# CT_Breakout_Board.net
KiCad netlist of a schematic drawn in Altium Designer
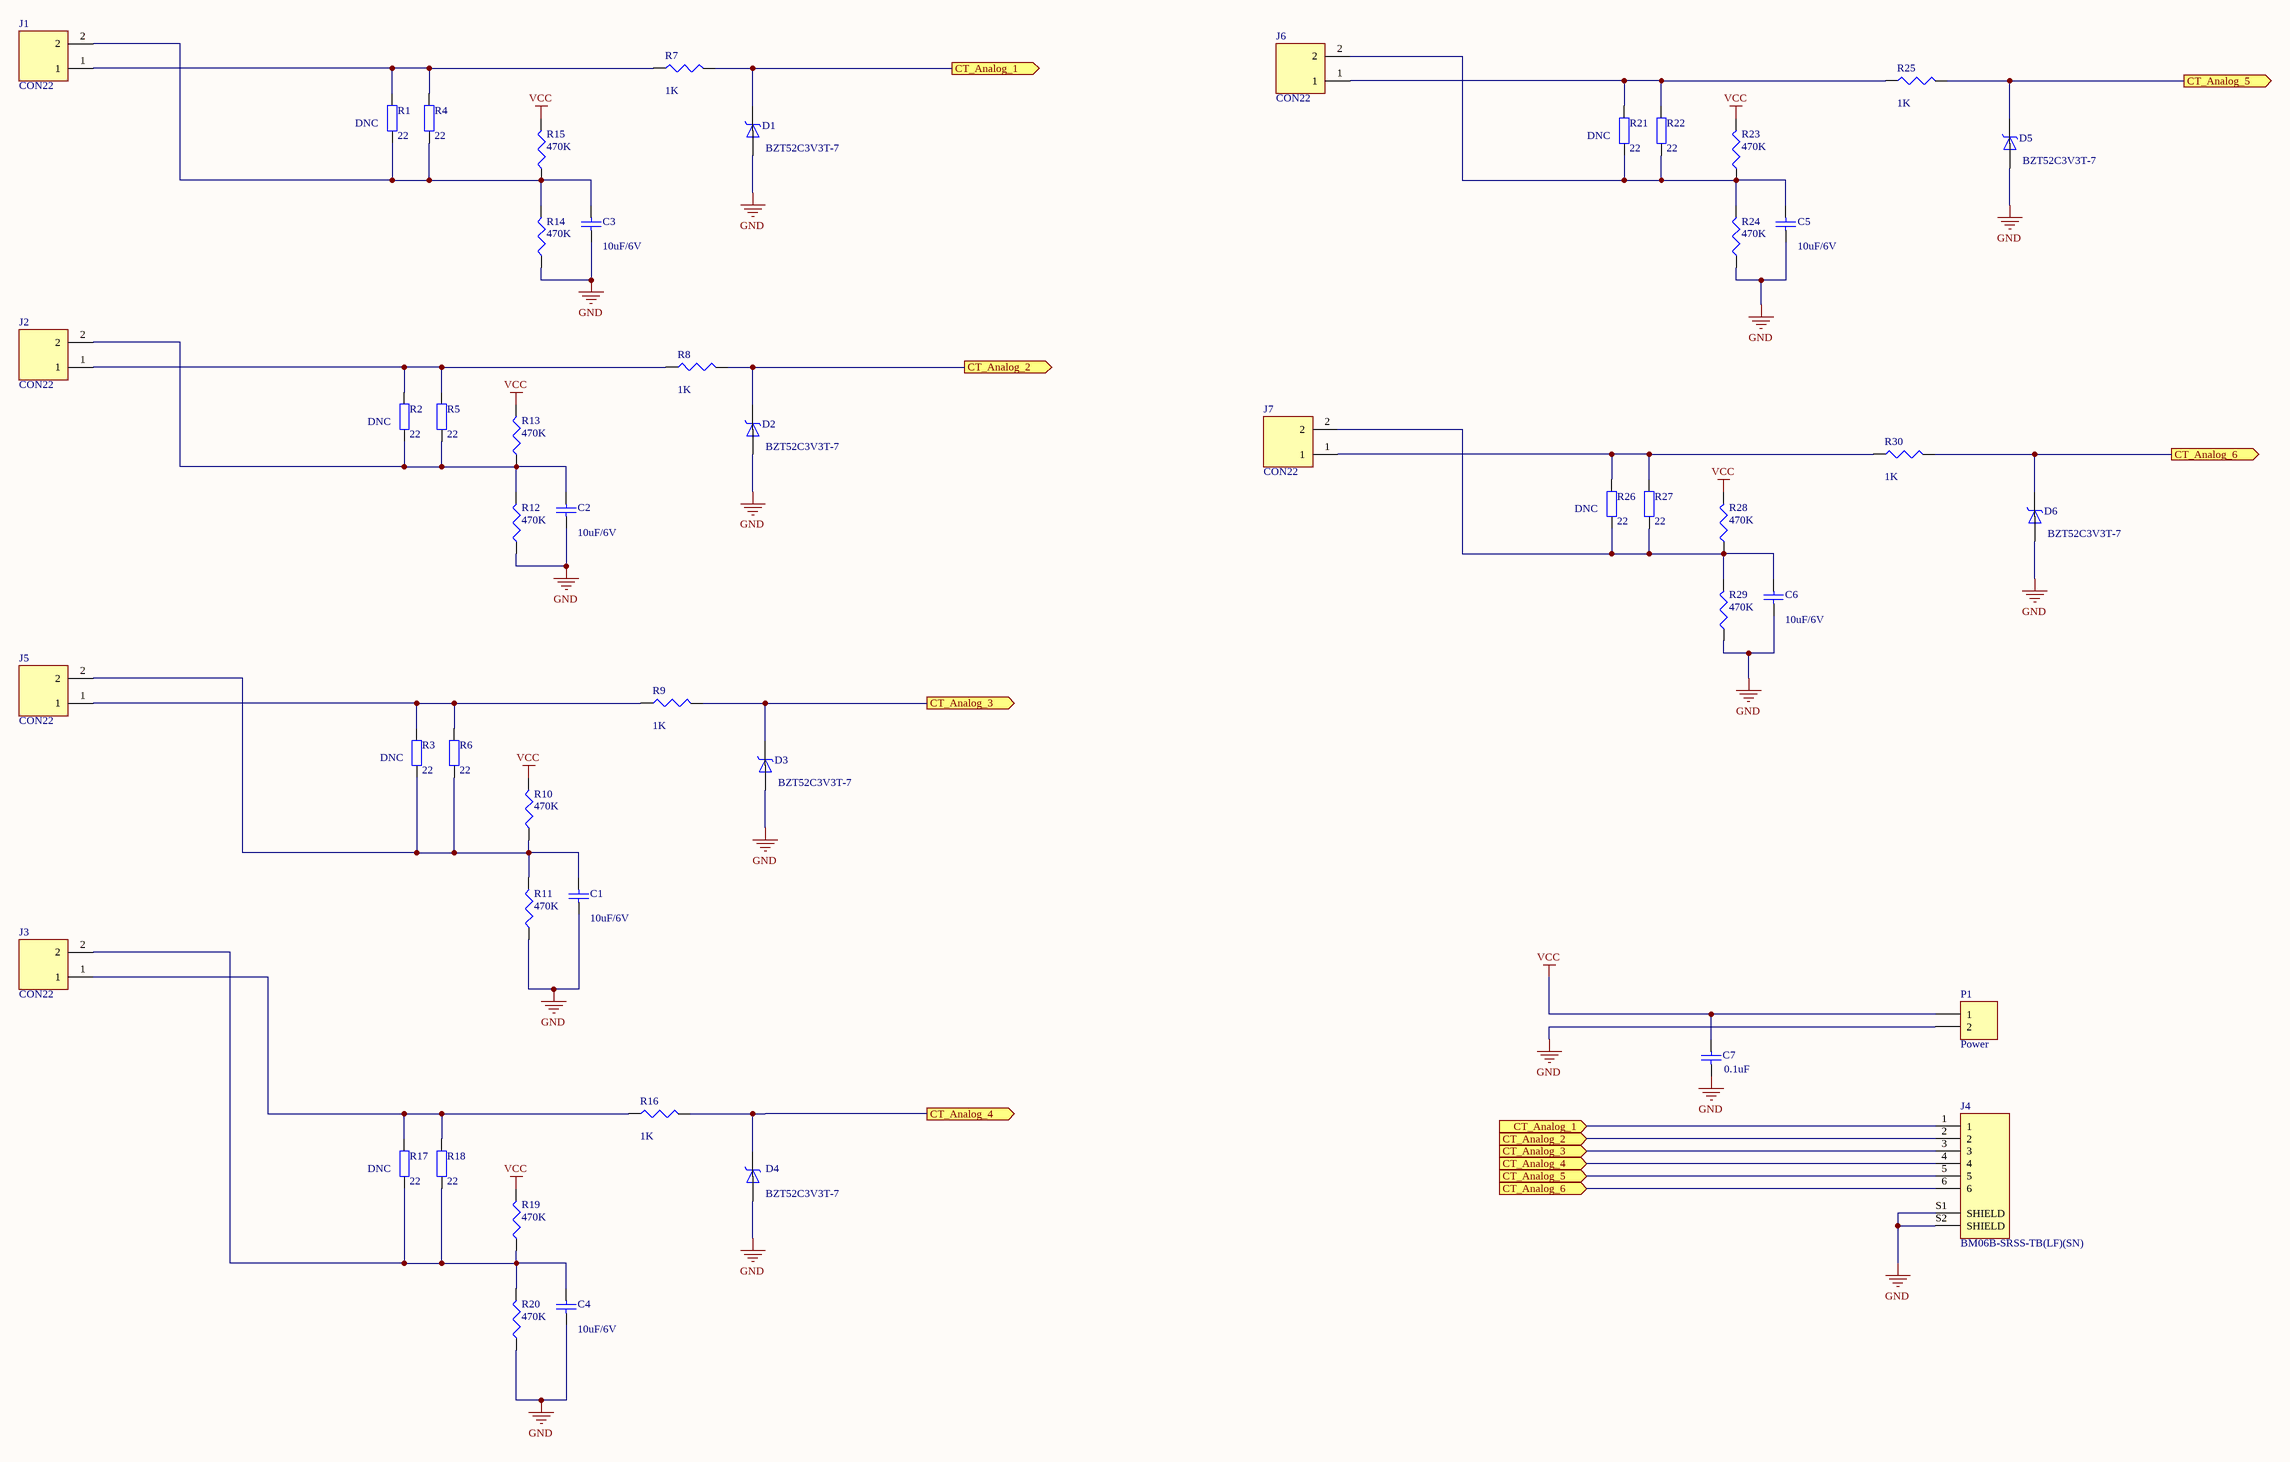
[diagram p0: CT_Breakout_Board.SchDoc]

(export (version "E")
  (design (tool "Eeschema 10.0.6"))
  (components
    (comp (ref "C1")
      (value "10uF/6V")
      (footprint "1608[0603]")
      (description "Capacitor (Semiconductor SIM Model)")
      (fields (field (name "Comment") "Cap Semi") (field (name "PUBLISHER") "Altium Limited"))
      (libsource (lib "Miscellaneous Devices") (part "Cap Semi"))
    )
    (comp (ref "C2")
      (value "10uF/6V")
      (footprint "1608[0603]")
      (description "Capacitor (Semiconductor SIM Model)")
      (fields (field (name "Comment") "Cap Semi") (field (name "PUBLISHER") "Altium Limited"))
      (libsource (lib "Miscellaneous Devices") (part "Cap Semi"))
    )
    (comp (ref "C3")
      (value "10uF/6V")
      (footprint "1608[0603]")
      (description "Capacitor (Semiconductor SIM Model)")
      (fields (field (name "Comment") "Cap Semi") (field (name "PUBLISHER") "Altium Limited"))
      (libsource (lib "Miscellaneous Devices") (part "Cap Semi"))
    )
    (comp (ref "C4")
      (value "10uF/6V")
      (footprint "1608[0603]")
      (description "Capacitor (Semiconductor SIM Model)")
      (fields (field (name "Comment") "Cap Semi") (field (name "PUBLISHER") "Altium Limited"))
      (libsource (lib "Miscellaneous Devices") (part "Cap Semi"))
    )
    (comp (ref "C5")
      (value "10uF/6V")
      (footprint "1608[0603]")
      (description "Capacitor (Semiconductor SIM Model)")
      (fields (field (name "Comment") "Cap Semi") (field (name "PUBLISHER") "Altium Limited"))
      (libsource (lib "Miscellaneous Devices") (part "Cap Semi"))
    )
    (comp (ref "C6")
      (value "10uF/6V")
      (footprint "1608[0603]")
      (description "Capacitor (Semiconductor SIM Model)")
      (fields (field (name "Comment") "Cap Semi") (field (name "PUBLISHER") "Altium Limited"))
      (libsource (lib "Miscellaneous Devices") (part "Cap Semi"))
    )
    (comp (ref "C7")
      (value "0.1uF")
      (footprint "1608[0603]")
      (description "Capacitor (Semiconductor SIM Model)")
      (fields (field (name "Comment") "Cap Semi") (field (name "PUBLISHER") "Altium Limited"))
      (libsource (lib "Miscellaneous Devices") (part "Cap Semi"))
    )
    (comp (ref "D1")
      (value "BZT52C3V3T-7")
      (footprint "SODFL1608X65N")
      (description "Zener Diode 3.3V 300mW Â±6% Surface Mount SOD-523")
      (fields (field (name "MF") "Diodes Inc."))
      (libsource (lib "BZT52C3V3T-7") (part "BZT52C3V3T-7"))
    )
    (comp (ref "D2")
      (value "BZT52C3V3T-7")
      (footprint "SODFL1608X65N")
      (description "Zener Diode 3.3V 300mW Â±6% Surface Mount SOD-523")
      (fields (field (name "MF") "Diodes Inc."))
      (libsource (lib "BZT52C3V3T-7") (part "BZT52C3V3T-7"))
    )
    (comp (ref "D3")
      (value "BZT52C3V3T-7")
      (footprint "SODFL1608X65N")
      (description "Zener Diode 3.3V 300mW Â±6% Surface Mount SOD-523")
      (fields (field (name "MF") "Diodes Inc."))
      (libsource (lib "BZT52C3V3T-7") (part "BZT52C3V3T-7"))
    )
    (comp (ref "D4")
      (value "BZT52C3V3T-7")
      (footprint "SODFL1608X65N")
      (description "Zener Diode 3.3V 300mW Â±6% Surface Mount SOD-523")
      (fields (field (name "MF") "Diodes Inc."))
      (libsource (lib "BZT52C3V3T-7") (part "BZT52C3V3T-7"))
    )
    (comp (ref "D5")
      (value "BZT52C3V3T-7")
      (footprint "SODFL1608X65N")
      (description "Zener Diode 3.3V 300mW Â±6% Surface Mount SOD-523")
      (fields (field (name "MF") "Diodes Inc."))
      (libsource (lib "BZT52C3V3T-7") (part "BZT52C3V3T-7"))
    )
    (comp (ref "D6")
      (value "BZT52C3V3T-7")
      (footprint "SODFL1608X65N")
      (description "Zener Diode 3.3V 300mW Â±6% Surface Mount SOD-523")
      (fields (field (name "MF") "Diodes Inc."))
      (libsource (lib "BZT52C3V3T-7") (part "BZT52C3V3T-7"))
    )
    (comp (ref "J1")
      (value "CON22")
      (footprint "HANDSON_KF301-2P")
      (description "2 Pin Terminal Block 5mm Pitch")
      (fields (field (name "MP") "KF301-2P") (field (name "MF") "Handson Technology"))
      (libsource (lib "KF301-2P") (part "KF301-2P"))
    )
    (comp (ref "J2")
      (value "CON22")
      (footprint "HANDSON_KF301-2P")
      (description "2 Pin Terminal Block 5mm Pitch")
      (fields (field (name "MP") "KF301-2P") (field (name "MF") "Handson Technology"))
      (libsource (lib "KF301-2P") (part "KF301-2P"))
    )
    (comp (ref "J3")
      (value "CON22")
      (footprint "HANDSON_KF301-2P")
      (description "2 Pin Terminal Block 5mm Pitch")
      (fields (field (name "MP") "KF301-2P") (field (name "MF") "Handson Technology"))
      (libsource (lib "KF301-2P") (part "KF301-2P"))
    )
    (comp (ref "J4")
      (value "BM06B-SRSS-TB(LF)(SN)")
      (footprint "JST_BM06B-SRSS-TB(LF)(SN)")
      (description "Connector Header Surface Mount 6 position 0.039 (1.00mm)")
      (fields (field (name "MF") "JST Sales"))
      (libsource (lib "BM06B-SRSS-TB_LF__SN_") (part "BM06B-SRSS-TB(LF)(SN)"))
    )
    (comp (ref "J5")
      (value "CON22")
      (footprint "HANDSON_KF301-2P")
      (description "2 Pin Terminal Block 5mm Pitch")
      (fields (field (name "MP") "KF301-2P") (field (name "MF") "Handson Technology"))
      (libsource (lib "KF301-2P") (part "KF301-2P"))
    )
    (comp (ref "J6")
      (value "CON22")
      (footprint "HANDSON_KF301-2P")
      (description "2 Pin Terminal Block 5mm Pitch")
      (fields (field (name "MP") "KF301-2P") (field (name "MF") "Handson Technology"))
      (libsource (lib "KF301-2P") (part "KF301-2P"))
    )
    (comp (ref "J7")
      (value "CON22")
      (footprint "HANDSON_KF301-2P")
      (description "2 Pin Terminal Block 5mm Pitch")
      (fields (field (name "MP") "KF301-2P") (field (name "MF") "Handson Technology"))
      (libsource (lib "KF301-2P") (part "KF301-2P"))
    )
    (comp (ref "P1")
      (value "Power")
      (footprint "HDR1X2")
      (description "Header, 2-Pin")
      (fields (field (name "PUBLISHER") "Altium Limited"))
      (libsource (lib "Miscellaneous Connectors") (part "Header 2"))
    )
    (comp (ref "R1")
      (value "DNC")
      (footprint "AXIAL-0.4")
      (description "Resistor")
      (fields (field (name "ALTIUM_VALUE") "22") (field (name "PUBLISHER") "Altium Limited"))
      (libsource (lib "Miscellaneous Devices") (part "Res2"))
    )
    (comp (ref "R2")
      (value "DNC")
      (footprint "AXIAL-0.4")
      (description "Resistor")
      (fields (field (name "ALTIUM_VALUE") "22") (field (name "PUBLISHER") "Altium Limited"))
      (libsource (lib "Miscellaneous Devices") (part "Res2"))
    )
    (comp (ref "R3")
      (value "DNC")
      (footprint "AXIAL-0.4")
      (description "Resistor")
      (fields (field (name "ALTIUM_VALUE") "22") (field (name "PUBLISHER") "Altium Limited"))
      (libsource (lib "Miscellaneous Devices") (part "Res2"))
    )
    (comp (ref "R4")
      (value "22")
      (footprint "AXIAL-0.4")
      (description "Resistor")
      (fields (field (name "PUBLISHER") "Altium Limited"))
      (libsource (lib "Miscellaneous Devices") (part "Res2"))
    )
    (comp (ref "R5")
      (value "22")
      (footprint "AXIAL-0.4")
      (description "Resistor")
      (fields (field (name "PUBLISHER") "Altium Limited"))
      (libsource (lib "Miscellaneous Devices") (part "Res2"))
    )
    (comp (ref "R6")
      (value "22")
      (footprint "AXIAL-0.4")
      (description "Resistor")
      (fields (field (name "PUBLISHER") "Altium Limited"))
      (libsource (lib "Miscellaneous Devices") (part "Res2"))
    )
    (comp (ref "R7")
      (value "1K")
      (footprint "J1-0603")
      (description "Resistor")
      (fields (field (name "Comment") "Res3") (field (name "PUBLISHER") "Altium Limited"))
      (libsource (lib "Miscellaneous Devices") (part "Res3"))
    )
    (comp (ref "R8")
      (value "1K")
      (footprint "J1-0603")
      (description "Resistor")
      (fields (field (name "Comment") "Res3") (field (name "PUBLISHER") "Altium Limited"))
      (libsource (lib "Miscellaneous Devices") (part "Res3"))
    )
    (comp (ref "R9")
      (value "1K")
      (footprint "J1-0603")
      (description "Resistor")
      (fields (field (name "Comment") "Res3") (field (name "PUBLISHER") "Altium Limited"))
      (libsource (lib "Miscellaneous Devices") (part "Res3"))
    )
    (comp (ref "R10")
      (value "470K")
      (footprint "J1-0603")
      (description "Resistor")
      (fields (field (name "Comment") "Res3") (field (name "PUBLISHER") "Altium Limited"))
      (libsource (lib "Miscellaneous Devices") (part "Res3"))
    )
    (comp (ref "R11")
      (value "470K")
      (footprint "J1-0603")
      (description "Resistor")
      (fields (field (name "Comment") "Res3") (field (name "PUBLISHER") "Altium Limited"))
      (libsource (lib "Miscellaneous Devices") (part "Res3"))
    )
    (comp (ref "R12")
      (value "470K")
      (footprint "J1-0603")
      (description "Resistor")
      (fields (field (name "Comment") "Res3") (field (name "PUBLISHER") "Altium Limited"))
      (libsource (lib "Miscellaneous Devices") (part "Res3"))
    )
    (comp (ref "R13")
      (value "470K")
      (footprint "J1-0603")
      (description "Resistor")
      (fields (field (name "Comment") "Res3") (field (name "PUBLISHER") "Altium Limited"))
      (libsource (lib "Miscellaneous Devices") (part "Res3"))
    )
    (comp (ref "R14")
      (value "470K")
      (footprint "J1-0603")
      (description "Resistor")
      (fields (field (name "Comment") "Res3") (field (name "PUBLISHER") "Altium Limited"))
      (libsource (lib "Miscellaneous Devices") (part "Res3"))
    )
    (comp (ref "R15")
      (value "470K")
      (footprint "J1-0603")
      (description "Resistor")
      (fields (field (name "Comment") "Res3") (field (name "PUBLISHER") "Altium Limited"))
      (libsource (lib "Miscellaneous Devices") (part "Res3"))
    )
    (comp (ref "R16")
      (value "1K")
      (footprint "J1-0603")
      (description "Resistor")
      (fields (field (name "Comment") "Res3") (field (name "PUBLISHER") "Altium Limited"))
      (libsource (lib "Miscellaneous Devices") (part "Res3"))
    )
    (comp (ref "R17")
      (value "DNC")
      (footprint "AXIAL-0.4")
      (description "Resistor")
      (fields (field (name "ALTIUM_VALUE") "22") (field (name "PUBLISHER") "Altium Limited"))
      (libsource (lib "Miscellaneous Devices") (part "Res2"))
    )
    (comp (ref "R18")
      (value "22")
      (footprint "AXIAL-0.4")
      (description "Resistor")
      (fields (field (name "PUBLISHER") "Altium Limited"))
      (libsource (lib "Miscellaneous Devices") (part "Res2"))
    )
    (comp (ref "R19")
      (value "470K")
      (footprint "J1-0603")
      (description "Resistor")
      (fields (field (name "Comment") "Res3") (field (name "PUBLISHER") "Altium Limited"))
      (libsource (lib "Miscellaneous Devices") (part "Res3"))
    )
    (comp (ref "R20")
      (value "470K")
      (footprint "J1-0603")
      (description "Resistor")
      (fields (field (name "Comment") "Res3") (field (name "PUBLISHER") "Altium Limited"))
      (libsource (lib "Miscellaneous Devices") (part "Res3"))
    )
    (comp (ref "R21")
      (value "DNC")
      (footprint "AXIAL-0.4")
      (description "Resistor")
      (fields (field (name "ALTIUM_VALUE") "22") (field (name "PUBLISHER") "Altium Limited"))
      (libsource (lib "Miscellaneous Devices") (part "Res2"))
    )
    (comp (ref "R22")
      (value "22")
      (footprint "AXIAL-0.4")
      (description "Resistor")
      (fields (field (name "PUBLISHER") "Altium Limited"))
      (libsource (lib "Miscellaneous Devices") (part "Res2"))
    )
    (comp (ref "R23")
      (value "470K")
      (footprint "J1-0603")
      (description "Resistor")
      (fields (field (name "Comment") "Res3") (field (name "PUBLISHER") "Altium Limited"))
      (libsource (lib "Miscellaneous Devices") (part "Res3"))
    )
    (comp (ref "R24")
      (value "470K")
      (footprint "J1-0603")
      (description "Resistor")
      (fields (field (name "Comment") "Res3") (field (name "PUBLISHER") "Altium Limited"))
      (libsource (lib "Miscellaneous Devices") (part "Res3"))
    )
    (comp (ref "R25")
      (value "1K")
      (footprint "J1-0603")
      (description "Resistor")
      (fields (field (name "Comment") "Res3") (field (name "PUBLISHER") "Altium Limited"))
      (libsource (lib "Miscellaneous Devices") (part "Res3"))
    )
    (comp (ref "R26")
      (value "DNC")
      (footprint "AXIAL-0.4")
      (description "Resistor")
      (fields (field (name "ALTIUM_VALUE") "22") (field (name "PUBLISHER") "Altium Limited"))
      (libsource (lib "Miscellaneous Devices") (part "Res2"))
    )
    (comp (ref "R27")
      (value "22")
      (footprint "AXIAL-0.4")
      (description "Resistor")
      (fields (field (name "PUBLISHER") "Altium Limited"))
      (libsource (lib "Miscellaneous Devices") (part "Res2"))
    )
    (comp (ref "R28")
      (value "470K")
      (footprint "J1-0603")
      (description "Resistor")
      (fields (field (name "Comment") "Res3") (field (name "PUBLISHER") "Altium Limited"))
      (libsource (lib "Miscellaneous Devices") (part "Res3"))
    )
    (comp (ref "R29")
      (value "470K")
      (footprint "J1-0603")
      (description "Resistor")
      (fields (field (name "Comment") "Res3") (field (name "PUBLISHER") "Altium Limited"))
      (libsource (lib "Miscellaneous Devices") (part "Res3"))
    )
    (comp (ref "R30")
      (value "1K")
      (footprint "J1-0603")
      (description "Resistor")
      (fields (field (name "Comment") "Res3") (field (name "PUBLISHER") "Altium Limited"))
      (libsource (lib "Miscellaneous Devices") (part "Res3"))
    )
  )
  (nets
    (net (code "1") (name "/CT_Analog_1") (class "Default")
      (node (ref "D1") (pin "C") (pinfunction "C_C") (pintype "passive"))
      (node (ref "J4") (pin "1") (pinfunction "1_1") (pintype "passive"))
      (node (ref "R7") (pin "2") (pinfunction "2_2") (pintype "passive"))
    )
    (net (code "2") (name "/CT_Analog_2") (class "Default")
      (node (ref "D2") (pin "C") (pinfunction "C_C") (pintype "passive"))
      (node (ref "J4") (pin "2") (pinfunction "2_2") (pintype "passive"))
      (node (ref "R8") (pin "2") (pinfunction "2_2") (pintype "passive"))
    )
    (net (code "3") (name "/CT_Analog_3") (class "Default")
      (node (ref "D3") (pin "C") (pinfunction "C_C") (pintype "passive"))
      (node (ref "J4") (pin "3") (pinfunction "3_3") (pintype "passive"))
      (node (ref "R9") (pin "2") (pinfunction "2_2") (pintype "passive"))
    )
    (net (code "4") (name "/CT_Analog_4") (class "Default")
      (node (ref "D4") (pin "C") (pinfunction "C_C") (pintype "passive"))
      (node (ref "J4") (pin "4") (pinfunction "4_4") (pintype "passive"))
      (node (ref "R16") (pin "2") (pinfunction "2_2") (pintype "passive"))
    )
    (net (code "5") (name "/CT_Analog_5") (class "Default")
      (node (ref "D5") (pin "C") (pinfunction "C_C") (pintype "passive"))
      (node (ref "J4") (pin "5") (pinfunction "5_5") (pintype "passive"))
      (node (ref "R25") (pin "2") (pinfunction "2_2") (pintype "passive"))
    )
    (net (code "6") (name "/CT_Analog_6") (class "Default")
      (node (ref "D6") (pin "C") (pinfunction "C_C") (pintype "passive"))
      (node (ref "J4") (pin "6") (pinfunction "6_6") (pintype "passive"))
      (node (ref "R30") (pin "2") (pinfunction "2_2") (pintype "passive"))
    )
    (net (code "7") (name "GND") (class "Default")
      (node (ref "C1") (pin "1") (pinfunction "1_1") (pintype "passive"))
      (node (ref "C2") (pin "1") (pinfunction "1_1") (pintype "passive"))
      (node (ref "C3") (pin "1") (pinfunction "1_1") (pintype "passive"))
      (node (ref "C4") (pin "1") (pinfunction "1_1") (pintype "passive"))
      (node (ref "C5") (pin "1") (pinfunction "1_1") (pintype "passive"))
      (node (ref "C6") (pin "1") (pinfunction "1_1") (pintype "passive"))
      (node (ref "C7") (pin "1") (pinfunction "1_1") (pintype "passive"))
      (node (ref "D1") (pin "A") (pinfunction "A_A") (pintype "passive"))
      (node (ref "D2") (pin "A") (pinfunction "A_A") (pintype "passive"))
      (node (ref "D3") (pin "A") (pinfunction "A_A") (pintype "passive"))
      (node (ref "D4") (pin "A") (pinfunction "A_A") (pintype "passive"))
      (node (ref "D5") (pin "A") (pinfunction "A_A") (pintype "passive"))
      (node (ref "D6") (pin "A") (pinfunction "A_A") (pintype "passive"))
      (node (ref "J4") (pin "S1") (pinfunction "SHIELD_S1") (pintype "passive"))
      (node (ref "J4") (pin "S2") (pinfunction "SHIELD_S2") (pintype "passive"))
      (node (ref "P1") (pin "2") (pinfunction "2_2") (pintype "passive"))
      (node (ref "R11") (pin "1") (pinfunction "1_1") (pintype "passive"))
      (node (ref "R12") (pin "1") (pinfunction "1_1") (pintype "passive"))
      (node (ref "R14") (pin "1") (pinfunction "1_1") (pintype "passive"))
      (node (ref "R20") (pin "1") (pinfunction "1_1") (pintype "passive"))
      (node (ref "R24") (pin "1") (pinfunction "1_1") (pintype "passive"))
      (node (ref "R29") (pin "1") (pinfunction "1_1") (pintype "passive"))
    )
    (net (code "8") (name "Net-(C1-Pad2)") (class "Default")
      (node (ref "C1") (pin "2") (pinfunction "2_2") (pintype "passive"))
      (node (ref "J5") (pin "2") (pinfunction "2_2") (pintype "passive"))
      (node (ref "R10") (pin "1") (pinfunction "1_1") (pintype "passive"))
      (node (ref "R11") (pin "2") (pinfunction "2_2") (pintype "passive"))
      (node (ref "R3") (pin "1") (pinfunction "1_1") (pintype "passive"))
      (node (ref "R6") (pin "1") (pinfunction "1_1") (pintype "passive"))
    )
    (net (code "9") (name "Net-(C2-Pad2)") (class "Default")
      (node (ref "C2") (pin "2") (pinfunction "2_2") (pintype "passive"))
      (node (ref "J2") (pin "2") (pinfunction "2_2") (pintype "passive"))
      (node (ref "R12") (pin "2") (pinfunction "2_2") (pintype "passive"))
      (node (ref "R13") (pin "1") (pinfunction "1_1") (pintype "passive"))
      (node (ref "R2") (pin "1") (pinfunction "1_1") (pintype "passive"))
      (node (ref "R5") (pin "1") (pinfunction "1_1") (pintype "passive"))
    )
    (net (code "10") (name "Net-(C3-Pad2)") (class "Default")
      (node (ref "C3") (pin "2") (pinfunction "2_2") (pintype "passive"))
      (node (ref "J1") (pin "2") (pinfunction "2_2") (pintype "passive"))
      (node (ref "R1") (pin "1") (pinfunction "1_1") (pintype "passive"))
      (node (ref "R14") (pin "2") (pinfunction "2_2") (pintype "passive"))
      (node (ref "R15") (pin "1") (pinfunction "1_1") (pintype "passive"))
      (node (ref "R4") (pin "1") (pinfunction "1_1") (pintype "passive"))
    )
    (net (code "11") (name "Net-(C4-Pad2)") (class "Default")
      (node (ref "C4") (pin "2") (pinfunction "2_2") (pintype "passive"))
      (node (ref "J3") (pin "2") (pinfunction "2_2") (pintype "passive"))
      (node (ref "R17") (pin "1") (pinfunction "1_1") (pintype "passive"))
      (node (ref "R18") (pin "1") (pinfunction "1_1") (pintype "passive"))
      (node (ref "R19") (pin "1") (pinfunction "1_1") (pintype "passive"))
      (node (ref "R20") (pin "2") (pinfunction "2_2") (pintype "passive"))
    )
    (net (code "12") (name "Net-(C5-Pad2)") (class "Default")
      (node (ref "C5") (pin "2") (pinfunction "2_2") (pintype "passive"))
      (node (ref "J6") (pin "2") (pinfunction "2_2") (pintype "passive"))
      (node (ref "R21") (pin "1") (pinfunction "1_1") (pintype "passive"))
      (node (ref "R22") (pin "1") (pinfunction "1_1") (pintype "passive"))
      (node (ref "R23") (pin "1") (pinfunction "1_1") (pintype "passive"))
      (node (ref "R24") (pin "2") (pinfunction "2_2") (pintype "passive"))
    )
    (net (code "13") (name "Net-(C6-Pad2)") (class "Default")
      (node (ref "C6") (pin "2") (pinfunction "2_2") (pintype "passive"))
      (node (ref "J7") (pin "2") (pinfunction "2_2") (pintype "passive"))
      (node (ref "R26") (pin "1") (pinfunction "1_1") (pintype "passive"))
      (node (ref "R27") (pin "1") (pinfunction "1_1") (pintype "passive"))
      (node (ref "R28") (pin "1") (pinfunction "1_1") (pintype "passive"))
      (node (ref "R29") (pin "2") (pinfunction "2_2") (pintype "passive"))
    )
    (net (code "14") (name "Net-(J1-Pad1)") (class "Default")
      (node (ref "J1") (pin "1") (pinfunction "1_1") (pintype "passive"))
      (node (ref "R1") (pin "2") (pinfunction "2_2") (pintype "passive"))
      (node (ref "R4") (pin "2") (pinfunction "2_2") (pintype "passive"))
      (node (ref "R7") (pin "1") (pinfunction "1_1") (pintype "passive"))
    )
    (net (code "15") (name "Net-(J2-Pad1)") (class "Default")
      (node (ref "J2") (pin "1") (pinfunction "1_1") (pintype "passive"))
      (node (ref "R2") (pin "2") (pinfunction "2_2") (pintype "passive"))
      (node (ref "R5") (pin "2") (pinfunction "2_2") (pintype "passive"))
      (node (ref "R8") (pin "1") (pinfunction "1_1") (pintype "passive"))
    )
    (net (code "16") (name "Net-(J3-Pad1)") (class "Default")
      (node (ref "J3") (pin "1") (pinfunction "1_1") (pintype "passive"))
      (node (ref "R16") (pin "1") (pinfunction "1_1") (pintype "passive"))
      (node (ref "R17") (pin "2") (pinfunction "2_2") (pintype "passive"))
      (node (ref "R18") (pin "2") (pinfunction "2_2") (pintype "passive"))
    )
    (net (code "17") (name "Net-(J5-Pad1)") (class "Default")
      (node (ref "J5") (pin "1") (pinfunction "1_1") (pintype "passive"))
      (node (ref "R3") (pin "2") (pinfunction "2_2") (pintype "passive"))
      (node (ref "R6") (pin "2") (pinfunction "2_2") (pintype "passive"))
      (node (ref "R9") (pin "1") (pinfunction "1_1") (pintype "passive"))
    )
    (net (code "18") (name "Net-(J6-Pad1)") (class "Default")
      (node (ref "J6") (pin "1") (pinfunction "1_1") (pintype "passive"))
      (node (ref "R21") (pin "2") (pinfunction "2_2") (pintype "passive"))
      (node (ref "R22") (pin "2") (pinfunction "2_2") (pintype "passive"))
      (node (ref "R25") (pin "1") (pinfunction "1_1") (pintype "passive"))
    )
    (net (code "19") (name "Net-(J7-Pad1)") (class "Default")
      (node (ref "J7") (pin "1") (pinfunction "1_1") (pintype "passive"))
      (node (ref "R26") (pin "2") (pinfunction "2_2") (pintype "passive"))
      (node (ref "R27") (pin "2") (pinfunction "2_2") (pintype "passive"))
      (node (ref "R30") (pin "1") (pinfunction "1_1") (pintype "passive"))
    )
    (net (code "20") (name "VCC") (class "Default")
      (node (ref "C7") (pin "2") (pinfunction "2_2") (pintype "passive"))
      (node (ref "P1") (pin "1") (pinfunction "1_1") (pintype "passive"))
      (node (ref "R10") (pin "2") (pinfunction "2_2") (pintype "passive"))
      (node (ref "R13") (pin "2") (pinfunction "2_2") (pintype "passive"))
      (node (ref "R15") (pin "2") (pinfunction "2_2") (pintype "passive"))
      (node (ref "R19") (pin "2") (pinfunction "2_2") (pintype "passive"))
      (node (ref "R23") (pin "2") (pinfunction "2_2") (pintype "passive"))
      (node (ref "R28") (pin "2") (pinfunction "2_2") (pintype "passive"))
    )
  )
)
